# graphic_stereo.net
KiCad netlist of a schematic drawn in EAGLE
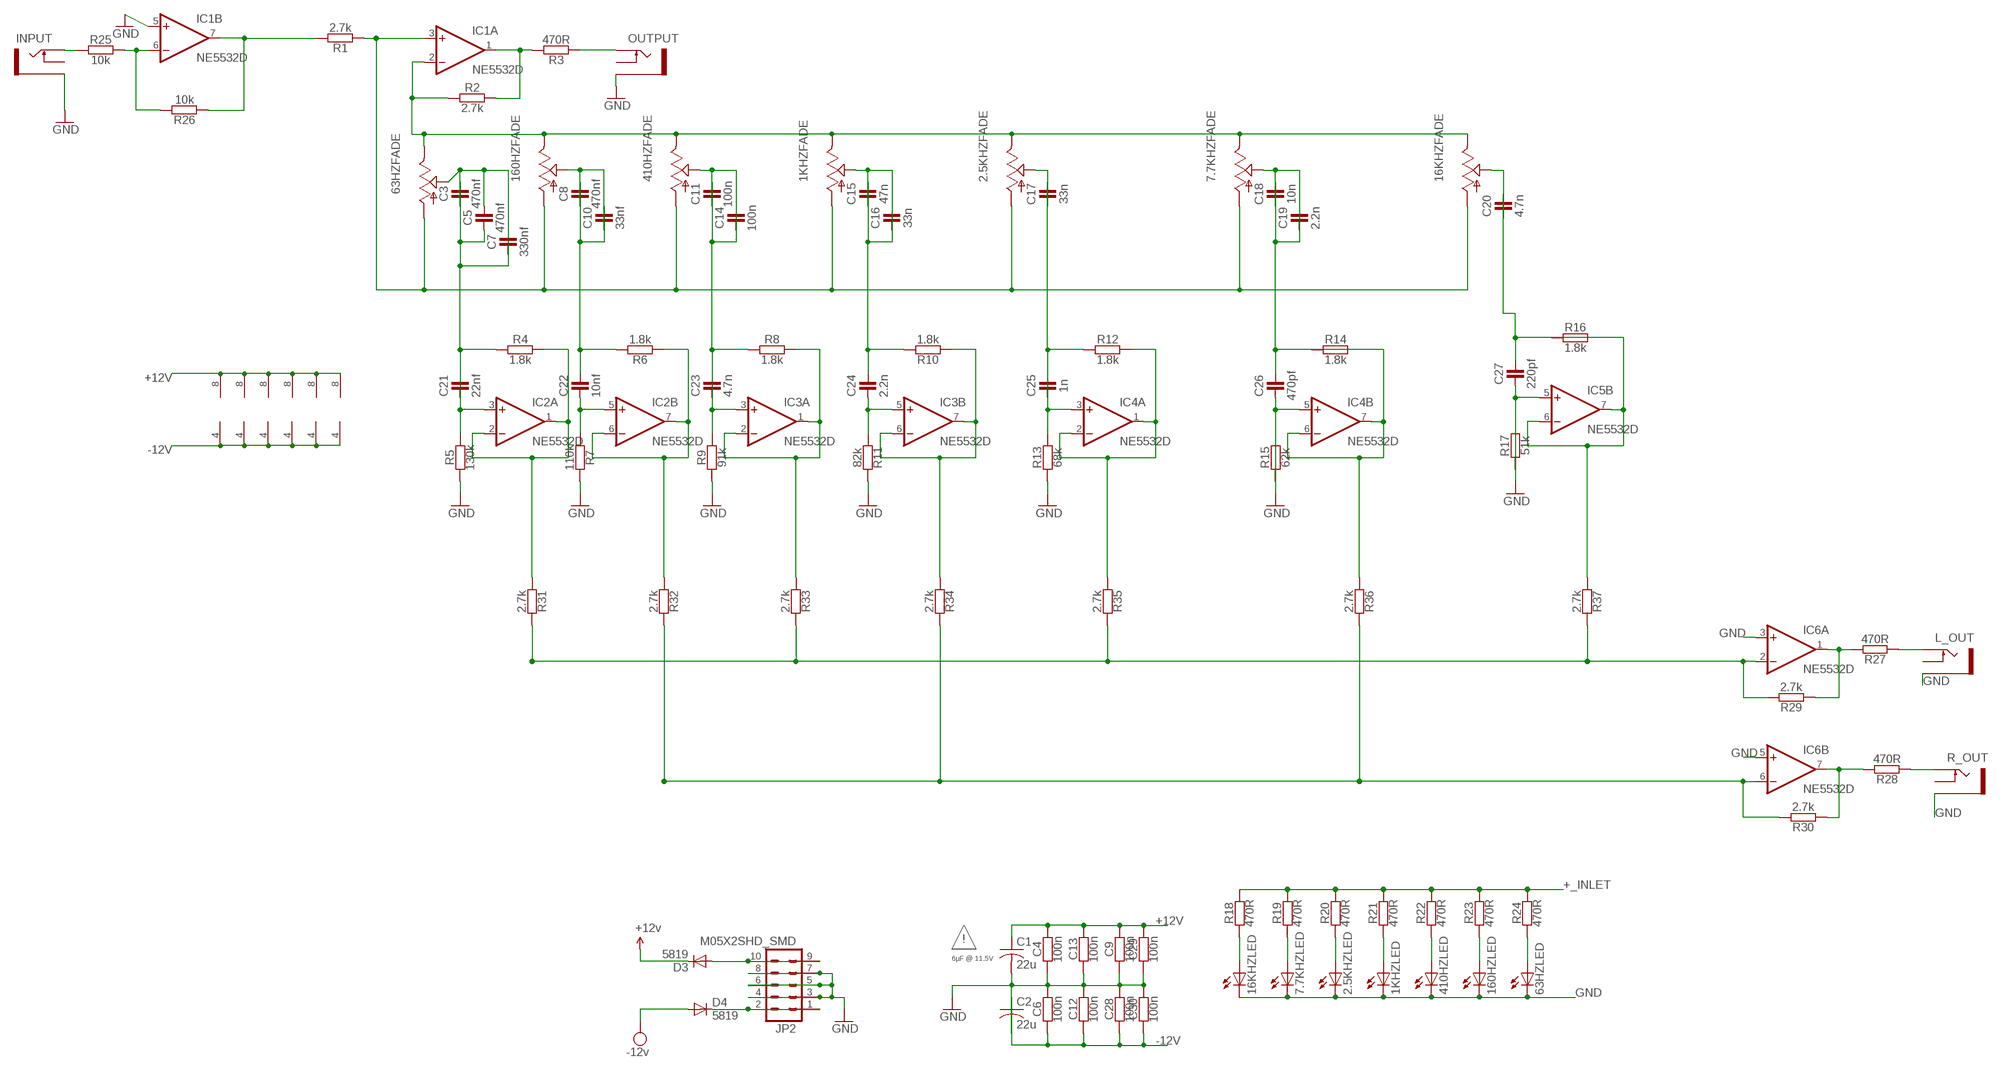
[diagram p0: schematic, sheet 1]

(export (version "E")
  (design (tool "Eeschema 10.0.6"))
  (components
    (comp (ref "1KHZ")
      (value "ALPHA_20MM_ILLUM_FADER")
      (footprint "eagle-import:ALPHA_ILL_FADER_20MM")
      (libsource (lib "eagle-import") (part "ALPHA_20MM_ILLUM_FADER"))
    )
    (comp (ref "2.5KHZ")
      (value "ALPHA_20MM_ILLUM_FADER")
      (footprint "eagle-import:ALPHA_ILL_FADER_20MM")
      (libsource (lib "eagle-import") (part "ALPHA_20MM_ILLUM_FADER"))
    )
    (comp (ref "7.7KHZ")
      (value "ALPHA_20MM_ILLUM_FADER")
      (footprint "eagle-import:ALPHA_ILL_FADER_20MM")
      (libsource (lib "eagle-import") (part "ALPHA_20MM_ILLUM_FADER"))
    )
    (comp (ref "16KHZ")
      (value "ALPHA_20MM_ILLUM_FADER")
      (footprint "eagle-import:ALPHA_ILL_FADER_20MM")
      (libsource (lib "eagle-import") (part "ALPHA_20MM_ILLUM_FADER"))
    )
    (comp (ref "63HZ")
      (value "ALPHA_20MM_ILLUM_FADER")
      (footprint "eagle-import:ALPHA_ILL_FADER_20MM")
      (libsource (lib "eagle-import") (part "ALPHA_20MM_ILLUM_FADER"))
    )
    (comp (ref "160HZ")
      (value "ALPHA_20MM_ILLUM_FADER")
      (footprint "eagle-import:ALPHA_ILL_FADER_20MM")
      (libsource (lib "eagle-import") (part "ALPHA_20MM_ILLUM_FADER"))
    )
    (comp (ref "410HZ")
      (value "ALPHA_20MM_ILLUM_FADER")
      (footprint "eagle-import:ALPHA_ILL_FADER_20MM")
      (libsource (lib "eagle-import") (part "ALPHA_20MM_ILLUM_FADER"))
    )
    (comp (ref "C1")
      (value "22u")
      (footprint "eagle-import:C1206")
      (libsource (lib "eagle-import") (part "C-USC1206"))
    )
    (comp (ref "C2")
      (value "22u")
      (footprint "eagle-import:C1206")
      (libsource (lib "eagle-import") (part "C-USC1206"))
    )
    (comp (ref "C3")
      (value "470nf")
      (footprint "eagle-import:C0805")
      (libsource (lib "eagle-import") (part "CAPACITOR-0805"))
    )
    (comp (ref "C4")
      (value "100n")
      (footprint "eagle-import:C0805")
      (libsource (lib "eagle-import") (part "RESISTOR-0805"))
    )
    (comp (ref "C5")
      (value "470nf")
      (footprint "eagle-import:C0805")
      (libsource (lib "eagle-import") (part "CAPACITOR-0805"))
    )
    (comp (ref "C6")
      (value "100n")
      (footprint "eagle-import:C0805")
      (libsource (lib "eagle-import") (part "RESISTOR-0805"))
    )
    (comp (ref "C7")
      (value "330nf")
      (footprint "eagle-import:C0805")
      (libsource (lib "eagle-import") (part "CAPACITOR-0805"))
    )
    (comp (ref "C8")
      (value "470nf")
      (footprint "eagle-import:C0805")
      (libsource (lib "eagle-import") (part "CAPACITOR-0805"))
    )
    (comp (ref "C9")
      (value "100n")
      (footprint "eagle-import:C0805")
      (libsource (lib "eagle-import") (part "RESISTOR-0805"))
    )
    (comp (ref "C10")
      (value "33nf")
      (footprint "eagle-import:C0805")
      (libsource (lib "eagle-import") (part "CAPACITOR-0805"))
    )
    (comp (ref "C11")
      (value "100n")
      (footprint "eagle-import:C0805")
      (libsource (lib "eagle-import") (part "CAPACITOR-0805"))
    )
    (comp (ref "C12")
      (value "100n")
      (footprint "eagle-import:C0805")
      (libsource (lib "eagle-import") (part "RESISTOR-0805"))
    )
    (comp (ref "C13")
      (value "100n")
      (footprint "eagle-import:C0805")
      (libsource (lib "eagle-import") (part "RESISTOR-0805"))
    )
    (comp (ref "C14")
      (value "100n")
      (footprint "eagle-import:C0805")
      (libsource (lib "eagle-import") (part "CAPACITOR-0805"))
    )
    (comp (ref "C15")
      (value "47n")
      (footprint "eagle-import:C0805")
      (libsource (lib "eagle-import") (part "CAPACITOR-0805"))
    )
    (comp (ref "C16")
      (value "33n")
      (footprint "eagle-import:C0805")
      (libsource (lib "eagle-import") (part "CAPACITOR-0805"))
    )
    (comp (ref "C17")
      (value "33n")
      (footprint "eagle-import:C0805")
      (libsource (lib "eagle-import") (part "CAPACITOR-0805"))
    )
    (comp (ref "C18")
      (value "10n")
      (footprint "eagle-import:C0805")
      (libsource (lib "eagle-import") (part "CAPACITOR-0805"))
    )
    (comp (ref "C19")
      (value "2.2n")
      (footprint "eagle-import:C0805")
      (libsource (lib "eagle-import") (part "CAPACITOR-0805"))
    )
    (comp (ref "C20")
      (value "4.7n")
      (footprint "eagle-import:C0805")
      (libsource (lib "eagle-import") (part "CAPACITOR-0805"))
    )
    (comp (ref "C21")
      (value "22nf")
      (footprint "eagle-import:C0805")
      (libsource (lib "eagle-import") (part "CAPACITOR-0805"))
    )
    (comp (ref "C22")
      (value "10nf")
      (footprint "eagle-import:C0805")
      (libsource (lib "eagle-import") (part "CAPACITOR-0805"))
    )
    (comp (ref "C23")
      (value "4.7n")
      (footprint "eagle-import:C0805")
      (libsource (lib "eagle-import") (part "CAPACITOR-0805"))
    )
    (comp (ref "C24")
      (value "2.2n")
      (footprint "eagle-import:C0805")
      (libsource (lib "eagle-import") (part "CAPACITOR-0805"))
    )
    (comp (ref "C25")
      (value "1n")
      (footprint "eagle-import:C0805")
      (libsource (lib "eagle-import") (part "CAPACITOR-0805"))
    )
    (comp (ref "C26")
      (value "470pf")
      (footprint "eagle-import:C0805")
      (libsource (lib "eagle-import") (part "CAPACITOR-0805"))
    )
    (comp (ref "C27")
      (value "220pf")
      (footprint "eagle-import:C0805")
      (libsource (lib "eagle-import") (part "CAPACITOR-0805"))
    )
    (comp (ref "C28")
      (value "100n")
      (footprint "eagle-import:C0805")
      (libsource (lib "eagle-import") (part "RESISTOR-0805"))
    )
    (comp (ref "C29")
      (value "100n")
      (footprint "eagle-import:C0805")
      (libsource (lib "eagle-import") (part "RESISTOR-0805"))
    )
    (comp (ref "C30")
      (value "100n")
      (footprint "eagle-import:C0805")
      (libsource (lib "eagle-import") (part "RESISTOR-0805"))
    )
    (comp (ref "D3")
      (value "5819")
      (footprint "eagle-import:SOD123")
      (libsource (lib "eagle-import") (part "DIODE-SOD123"))
    )
    (comp (ref "D4")
      (value "5819")
      (footprint "eagle-import:SOD123")
      (libsource (lib "eagle-import") (part "DIODE-SOD123"))
    )
    (comp (ref "IC1")
      (value "NE5532D")
      (footprint "eagle-import:SO08")
      (libsource (lib "eagle-import") (part "NE5532D"))
    )
    (comp (ref "IC2")
      (value "NE5532D")
      (footprint "eagle-import:SO08")
      (libsource (lib "eagle-import") (part "NE5532D"))
    )
    (comp (ref "IC3")
      (value "NE5532D")
      (footprint "eagle-import:SO08")
      (libsource (lib "eagle-import") (part "NE5532D"))
    )
    (comp (ref "IC4")
      (value "NE5532D")
      (footprint "eagle-import:SO08")
      (libsource (lib "eagle-import") (part "NE5532D"))
    )
    (comp (ref "IC5")
      (value "NE5532D")
      (footprint "eagle-import:SO08")
      (libsource (lib "eagle-import") (part "NE5532D"))
    )
    (comp (ref "IC6")
      (value "NE5532D")
      (footprint "eagle-import:SO08")
      (libsource (lib "eagle-import") (part "NE5532D"))
    )
    (comp (ref "INPUT")
      (value "THONKICONNNEW")
      (footprint "eagle-import:WQP-PJ301M-12_JACK")
      (libsource (lib "eagle-import") (part "THONKICONNNEW"))
    )
    (comp (ref "JP2")
      (value "M05X2SHD_SMD")
      (footprint "eagle-import:2X5-SHROUDED_SMD")
      (libsource (lib "eagle-import") (part "M05X2SHD_SMD"))
    )
    (comp (ref "L_OUT")
      (value "THONKICONNNEW")
      (footprint "eagle-import:WQP-PJ301M-12_JACK")
      (libsource (lib "eagle-import") (part "THONKICONNNEW"))
    )
    (comp (ref "OUTPUT")
      (value "THONKICONNNEW")
      (footprint "eagle-import:WQP-PJ301M-12_JACK")
      (libsource (lib "eagle-import") (part "THONKICONNNEW"))
    )
    (comp (ref "R1")
      (value "2.7k")
      (footprint "eagle-import:C0805")
      (libsource (lib "eagle-import") (part "RESISTOR-0805"))
    )
    (comp (ref "R2")
      (value "2.7k")
      (footprint "eagle-import:C0805")
      (libsource (lib "eagle-import") (part "RESISTOR-0805"))
    )
    (comp (ref "R3")
      (value "470R")
      (footprint "eagle-import:C0805")
      (libsource (lib "eagle-import") (part "RESISTOR-0805"))
    )
    (comp (ref "R4")
      (value "1.8k")
      (footprint "eagle-import:C0805")
      (libsource (lib "eagle-import") (part "RESISTOR-0805"))
    )
    (comp (ref "R5")
      (value "130k")
      (footprint "eagle-import:C0805")
      (libsource (lib "eagle-import") (part "RESISTOR-0805"))
    )
    (comp (ref "R6")
      (value "1.8k")
      (footprint "eagle-import:C0805")
      (libsource (lib "eagle-import") (part "RESISTOR-0805"))
    )
    (comp (ref "R7")
      (value "110k")
      (footprint "eagle-import:C0805")
      (libsource (lib "eagle-import") (part "RESISTOR-0805"))
    )
    (comp (ref "R8")
      (value "1.8k")
      (footprint "eagle-import:C0805")
      (libsource (lib "eagle-import") (part "RESISTOR-0805"))
    )
    (comp (ref "R9")
      (value "91k")
      (footprint "eagle-import:C0805")
      (libsource (lib "eagle-import") (part "RESISTOR-0805"))
    )
    (comp (ref "R10")
      (value "1.8k")
      (footprint "eagle-import:C0805")
      (libsource (lib "eagle-import") (part "RESISTOR-0805"))
    )
    (comp (ref "R11")
      (value "82k")
      (footprint "eagle-import:C0805")
      (libsource (lib "eagle-import") (part "RESISTOR-0805"))
    )
    (comp (ref "R12")
      (value "1.8k")
      (footprint "eagle-import:C0805")
      (libsource (lib "eagle-import") (part "RESISTOR-0805"))
    )
    (comp (ref "R13")
      (value "68k")
      (footprint "eagle-import:C0805")
      (libsource (lib "eagle-import") (part "RESISTOR-0805"))
    )
    (comp (ref "R14")
      (value "1.8k")
      (footprint "eagle-import:C0805")
      (libsource (lib "eagle-import") (part "RESISTOR-0805"))
    )
    (comp (ref "R15")
      (value "62k")
      (footprint "eagle-import:C0805")
      (libsource (lib "eagle-import") (part "RESISTOR-0805"))
    )
    (comp (ref "R16")
      (value "1.8k")
      (footprint "eagle-import:C0805")
      (libsource (lib "eagle-import") (part "RESISTOR-0805"))
    )
    (comp (ref "R17")
      (value "51k")
      (footprint "eagle-import:C0805")
      (libsource (lib "eagle-import") (part "RESISTOR-0805"))
    )
    (comp (ref "R18")
      (value "470R")
      (footprint "eagle-import:C0805")
      (libsource (lib "eagle-import") (part "RESISTOR-0805"))
    )
    (comp (ref "R19")
      (value "470R")
      (footprint "eagle-import:C0805")
      (libsource (lib "eagle-import") (part "RESISTOR-0805"))
    )
    (comp (ref "R20")
      (value "470R")
      (footprint "eagle-import:C0805")
      (libsource (lib "eagle-import") (part "RESISTOR-0805"))
    )
    (comp (ref "R21")
      (value "470R")
      (footprint "eagle-import:C0805")
      (libsource (lib "eagle-import") (part "RESISTOR-0805"))
    )
    (comp (ref "R22")
      (value "470R")
      (footprint "eagle-import:C0805")
      (libsource (lib "eagle-import") (part "RESISTOR-0805"))
    )
    (comp (ref "R23")
      (value "470R")
      (footprint "eagle-import:C0805")
      (libsource (lib "eagle-import") (part "RESISTOR-0805"))
    )
    (comp (ref "R24")
      (value "470R")
      (footprint "eagle-import:C0805")
      (libsource (lib "eagle-import") (part "RESISTOR-0805"))
    )
    (comp (ref "R25")
      (value "10k")
      (footprint "eagle-import:C0805")
      (libsource (lib "eagle-import") (part "RESISTOR-0805"))
    )
    (comp (ref "R26")
      (value "10k")
      (footprint "eagle-import:C0805")
      (libsource (lib "eagle-import") (part "RESISTOR-0805"))
    )
    (comp (ref "R27")
      (value "470R")
      (footprint "eagle-import:C0805")
      (libsource (lib "eagle-import") (part "RESISTOR-0805"))
    )
    (comp (ref "R28")
      (value "470R")
      (footprint "eagle-import:C0805")
      (libsource (lib "eagle-import") (part "RESISTOR-0805"))
    )
    (comp (ref "R29")
      (value "2.7k")
      (footprint "eagle-import:C0805")
      (libsource (lib "eagle-import") (part "RESISTOR-0805"))
    )
    (comp (ref "R30")
      (value "2.7k")
      (footprint "eagle-import:C0805")
      (libsource (lib "eagle-import") (part "RESISTOR-0805"))
    )
    (comp (ref "R31")
      (value "2.7k")
      (footprint "eagle-import:C0805")
      (libsource (lib "eagle-import") (part "RESISTOR-0805"))
    )
    (comp (ref "R32")
      (value "2.7k")
      (footprint "eagle-import:C0805")
      (libsource (lib "eagle-import") (part "RESISTOR-0805"))
    )
    (comp (ref "R33")
      (value "2.7k")
      (footprint "eagle-import:C0805")
      (libsource (lib "eagle-import") (part "RESISTOR-0805"))
    )
    (comp (ref "R34")
      (value "2.7k")
      (footprint "eagle-import:C0805")
      (libsource (lib "eagle-import") (part "RESISTOR-0805"))
    )
    (comp (ref "R35")
      (value "2.7k")
      (footprint "eagle-import:C0805")
      (libsource (lib "eagle-import") (part "RESISTOR-0805"))
    )
    (comp (ref "R36")
      (value "2.7k")
      (footprint "eagle-import:C0805")
      (libsource (lib "eagle-import") (part "RESISTOR-0805"))
    )
    (comp (ref "R37")
      (value "2.7k")
      (footprint "eagle-import:C0805")
      (libsource (lib "eagle-import") (part "RESISTOR-0805"))
    )
    (comp (ref "R_OUT")
      (value "THONKICONNNEW")
      (footprint "eagle-import:WQP-PJ301M-12_JACK")
      (libsource (lib "eagle-import") (part "THONKICONNNEW"))
    )
  )
  (nets
    (net (code "1") (name "+12v") (class "Default")
      (node (ref "C1") (pin "1") (pinfunction "1_1") (pintype "passive"))
      (node (ref "C13") (pin "2") (pinfunction "2_2") (pintype "passive"))
      (node (ref "C29") (pin "2") (pinfunction "2_2") (pintype "passive"))
      (node (ref "C4") (pin "2") (pinfunction "2_2") (pintype "passive"))
      (node (ref "C9") (pin "2") (pinfunction "2_2") (pintype "passive"))
      (node (ref "D3") (pin "C") (pinfunction "C_C") (pintype "passive"))
      (node (ref "IC1") (pin "8") (pinfunction "V+_8") (pintype "power_in"))
      (node (ref "IC2") (pin "8") (pinfunction "V+_8") (pintype "power_in"))
      (node (ref "IC3") (pin "8") (pinfunction "V+_8") (pintype "power_in"))
      (node (ref "IC4") (pin "8") (pinfunction "V+_8") (pintype "power_in"))
      (node (ref "IC5") (pin "8") (pinfunction "V+_8") (pintype "power_in"))
      (node (ref "IC6") (pin "8") (pinfunction "V+_8") (pintype "power_in"))
    )
    (net (code "2") (name "-12v") (class "Default")
      (node (ref "C12") (pin "1") (pinfunction "1_1") (pintype "passive"))
      (node (ref "C2") (pin "1") (pinfunction "1_1") (pintype "passive"))
      (node (ref "C28") (pin "1") (pinfunction "1_1") (pintype "passive"))
      (node (ref "C30") (pin "1") (pinfunction "1_1") (pintype "passive"))
      (node (ref "C6") (pin "1") (pinfunction "1_1") (pintype "passive"))
      (node (ref "D4") (pin "A") (pinfunction "A_A") (pintype "passive"))
      (node (ref "IC1") (pin "4") (pinfunction "V-_4") (pintype "power_in"))
      (node (ref "IC2") (pin "4") (pinfunction "V-_4") (pintype "power_in"))
      (node (ref "IC3") (pin "4") (pinfunction "V-_4") (pintype "power_in"))
      (node (ref "IC4") (pin "4") (pinfunction "V-_4") (pintype "power_in"))
      (node (ref "IC5") (pin "4") (pinfunction "V-_4") (pintype "power_in"))
      (node (ref "IC6") (pin "4") (pinfunction "V-_4") (pintype "power_in"))
    )
    (net (code "3") (name "/+_INLET") (class "Default")
      (node (ref "D3") (pin "A") (pinfunction "A_A") (pintype "passive"))
      (node (ref "JP2") (pin "10") (pinfunction "10_10") (pintype "passive"))
      (node (ref "JP2") (pin "9") (pinfunction "9_9") (pintype "passive"))
      (node (ref "R18") (pin "2") (pinfunction "2_2") (pintype "passive"))
      (node (ref "R19") (pin "2") (pinfunction "2_2") (pintype "passive"))
      (node (ref "R20") (pin "2") (pinfunction "2_2") (pintype "passive"))
      (node (ref "R21") (pin "2") (pinfunction "2_2") (pintype "passive"))
      (node (ref "R22") (pin "2") (pinfunction "2_2") (pintype "passive"))
      (node (ref "R23") (pin "2") (pinfunction "2_2") (pintype "passive"))
      (node (ref "R24") (pin "2") (pinfunction "2_2") (pintype "passive"))
    )
    (net (code "4") (name "GND") (class "Default")
      (node (ref "160HZ") (pin "E") (pinfunction "C_E") (pintype "passive"))
      (node (ref "16KHZ") (pin "E") (pinfunction "C_E") (pintype "passive"))
      (node (ref "1KHZ") (pin "E") (pinfunction "C_E") (pintype "passive"))
      (node (ref "2.5KHZ") (pin "E") (pinfunction "C_E") (pintype "passive"))
      (node (ref "410HZ") (pin "E") (pinfunction "C_E") (pintype "passive"))
      (node (ref "63HZ") (pin "E") (pinfunction "C_E") (pintype "passive"))
      (node (ref "7.7KHZ") (pin "E") (pinfunction "C_E") (pintype "passive"))
      (node (ref "C1") (pin "2") (pinfunction "2_2") (pintype "passive"))
      (node (ref "C12") (pin "2") (pinfunction "2_2") (pintype "passive"))
      (node (ref "C13") (pin "1") (pinfunction "1_1") (pintype "passive"))
      (node (ref "C2") (pin "2") (pinfunction "2_2") (pintype "passive"))
      (node (ref "C28") (pin "2") (pinfunction "2_2") (pintype "passive"))
      (node (ref "C29") (pin "1") (pinfunction "1_1") (pintype "passive"))
      (node (ref "C30") (pin "2") (pinfunction "2_2") (pintype "passive"))
      (node (ref "C4") (pin "1") (pinfunction "1_1") (pintype "passive"))
      (node (ref "C6") (pin "2") (pinfunction "2_2") (pintype "passive"))
      (node (ref "C9") (pin "1") (pinfunction "1_1") (pintype "passive"))
      (node (ref "IC1") (pin "5") (pinfunction "+IN_5") (pintype "input"))
      (node (ref "IC6") (pin "3") (pinfunction "+IN_3") (pintype "input"))
      (node (ref "IC6") (pin "5") (pinfunction "+IN_5") (pintype "input"))
      (node (ref "INPUT") (pin "P$3_SLEEVE") (pinfunction "SLEEVE_P$3_SLEEVE") (pintype "passive"))
      (node (ref "JP2") (pin "3") (pinfunction "3_3") (pintype "passive"))
      (node (ref "JP2") (pin "4") (pinfunction "4_4") (pintype "passive"))
      (node (ref "JP2") (pin "5") (pinfunction "5_5") (pintype "passive"))
      (node (ref "JP2") (pin "6") (pinfunction "6_6") (pintype "passive"))
      (node (ref "JP2") (pin "7") (pinfunction "7_7") (pintype "passive"))
      (node (ref "JP2") (pin "8") (pinfunction "8_8") (pintype "passive"))
      (node (ref "L_OUT") (pin "P$3_SLEEVE") (pinfunction "SLEEVE_P$3_SLEEVE") (pintype "passive"))
      (node (ref "OUTPUT") (pin "P$3_SLEEVE") (pinfunction "SLEEVE_P$3_SLEEVE") (pintype "passive"))
      (node (ref "R11") (pin "2") (pinfunction "2_2") (pintype "passive"))
      (node (ref "R13") (pin "1") (pinfunction "1_1") (pintype "passive"))
      (node (ref "R15") (pin "2") (pinfunction "2_2") (pintype "passive"))
      (node (ref "R17") (pin "2") (pinfunction "2_2") (pintype "passive"))
      (node (ref "R5") (pin "1") (pinfunction "1_1") (pintype "passive"))
      (node (ref "R7") (pin "2") (pinfunction "2_2") (pintype "passive"))
      (node (ref "R9") (pin "1") (pinfunction "1_1") (pintype "passive"))
      (node (ref "R_OUT") (pin "P$3_SLEEVE") (pinfunction "SLEEVE_P$3_SLEEVE") (pintype "passive"))
    )
    (net (code "5") (name "Net-(1KHZA-S)") (class "Default")
      (node (ref "1KHZ") (pin "2") (pinfunction "S_2") (pintype "passive"))
      (node (ref "C15") (pin "1") (pinfunction "1_1") (pintype "passive"))
      (node (ref "C16") (pin "1") (pinfunction "1_1") (pintype "passive"))
    )
    (net (code "6") (name "Net-(1KHZB-A)") (class "Default")
      (node (ref "1KHZ") (pin "B") (pinfunction "A_B") (pintype "passive"))
      (node (ref "R21") (pin "1") (pinfunction "1_1") (pintype "passive"))
    )
    (net (code "7") (name "Net-(2.5KHZA-S)") (class "Default")
      (node (ref "2.5KHZ") (pin "2") (pinfunction "S_2") (pintype "passive"))
      (node (ref "C17") (pin "1") (pinfunction "1_1") (pintype "passive"))
    )
    (net (code "8") (name "Net-(2.5KHZB-A)") (class "Default")
      (node (ref "2.5KHZ") (pin "B") (pinfunction "A_B") (pintype "passive"))
      (node (ref "R20") (pin "1") (pinfunction "1_1") (pintype "passive"))
    )
    (net (code "9") (name "Net-(7.7KHZA-S)") (class "Default")
      (node (ref "7.7KHZ") (pin "2") (pinfunction "S_2") (pintype "passive"))
      (node (ref "C18") (pin "1") (pinfunction "1_1") (pintype "passive"))
      (node (ref "C19") (pin "1") (pinfunction "1_1") (pintype "passive"))
    )
    (net (code "10") (name "Net-(7.7KHZB-A)") (class "Default")
      (node (ref "7.7KHZ") (pin "B") (pinfunction "A_B") (pintype "passive"))
      (node (ref "R19") (pin "1") (pinfunction "1_1") (pintype "passive"))
    )
    (net (code "11") (name "Net-(16KHZA-S)") (class "Default")
      (node (ref "16KHZ") (pin "2") (pinfunction "S_2") (pintype "passive"))
      (node (ref "C20") (pin "1") (pinfunction "1_1") (pintype "passive"))
    )
    (net (code "12") (name "Net-(16KHZB-A)") (class "Default")
      (node (ref "16KHZ") (pin "B") (pinfunction "A_B") (pintype "passive"))
      (node (ref "R18") (pin "1") (pinfunction "1_1") (pintype "passive"))
    )
    (net (code "13") (name "Net-(63HZA-S)") (class "Default")
      (node (ref "63HZ") (pin "2") (pinfunction "S_2") (pintype "passive"))
      (node (ref "C3") (pin "1") (pinfunction "1_1") (pintype "passive"))
      (node (ref "C5") (pin "2") (pinfunction "2_2") (pintype "passive"))
      (node (ref "C7") (pin "1") (pinfunction "1_1") (pintype "passive"))
    )
    (net (code "14") (name "Net-(63HZB-A)") (class "Default")
      (node (ref "63HZ") (pin "B") (pinfunction "A_B") (pintype "passive"))
      (node (ref "R24") (pin "1") (pinfunction "1_1") (pintype "passive"))
    )
    (net (code "15") (name "Net-(160HZA-A)") (class "Default")
      (node (ref "160HZ") (pin "3") (pinfunction "A_3") (pintype "passive"))
      (node (ref "16KHZ") (pin "3") (pinfunction "A_3") (pintype "passive"))
      (node (ref "1KHZ") (pin "3") (pinfunction "A_3") (pintype "passive"))
      (node (ref "2.5KHZ") (pin "3") (pinfunction "A_3") (pintype "passive"))
      (node (ref "410HZ") (pin "3") (pinfunction "A_3") (pintype "passive"))
      (node (ref "63HZ") (pin "3") (pinfunction "A_3") (pintype "passive"))
      (node (ref "7.7KHZ") (pin "3") (pinfunction "A_3") (pintype "passive"))
      (node (ref "IC1") (pin "3") (pinfunction "+IN_3") (pintype "input"))
      (node (ref "R1") (pin "1") (pinfunction "1_1") (pintype "passive"))
    )
    (net (code "16") (name "Net-(160HZA-E)") (class "Default")
      (node (ref "160HZ") (pin "1") (pinfunction "E_1") (pintype "passive"))
      (node (ref "16KHZ") (pin "1") (pinfunction "E_1") (pintype "passive"))
      (node (ref "1KHZ") (pin "1") (pinfunction "E_1") (pintype "passive"))
      (node (ref "2.5KHZ") (pin "1") (pinfunction "E_1") (pintype "passive"))
      (node (ref "410HZ") (pin "1") (pinfunction "E_1") (pintype "passive"))
      (node (ref "63HZ") (pin "1") (pinfunction "E_1") (pintype "passive"))
      (node (ref "7.7KHZ") (pin "1") (pinfunction "E_1") (pintype "passive"))
      (node (ref "IC1") (pin "2") (pinfunction "-IN_2") (pintype "input"))
      (node (ref "R2") (pin "1") (pinfunction "1_1") (pintype "passive"))
    )
    (net (code "17") (name "Net-(160HZA-S)") (class "Default")
      (node (ref "160HZ") (pin "2") (pinfunction "S_2") (pintype "passive"))
      (node (ref "C10") (pin "1") (pinfunction "1_1") (pintype "passive"))
      (node (ref "C8") (pin "1") (pinfunction "1_1") (pintype "passive"))
    )
    (net (code "18") (name "Net-(160HZB-A)") (class "Default")
      (node (ref "160HZ") (pin "B") (pinfunction "A_B") (pintype "passive"))
      (node (ref "R23") (pin "1") (pinfunction "1_1") (pintype "passive"))
    )
    (net (code "19") (name "Net-(410HZA-S)") (class "Default")
      (node (ref "410HZ") (pin "2") (pinfunction "S_2") (pintype "passive"))
      (node (ref "C11") (pin "1") (pinfunction "1_1") (pintype "passive"))
      (node (ref "C14") (pin "1") (pinfunction "1_1") (pintype "passive"))
    )
    (net (code "20") (name "Net-(410HZB-A)") (class "Default")
      (node (ref "410HZ") (pin "B") (pinfunction "A_B") (pintype "passive"))
      (node (ref "R22") (pin "1") (pinfunction "1_1") (pintype "passive"))
    )
    (net (code "21") (name "Net-(C10-Pad2)") (class "Default")
      (node (ref "C10") (pin "2") (pinfunction "2_2") (pintype "passive"))
      (node (ref "C22") (pin "2") (pinfunction "2_2") (pintype "passive"))
      (node (ref "C8") (pin "2") (pinfunction "2_2") (pintype "passive"))
      (node (ref "R6") (pin "2") (pinfunction "2_2") (pintype "passive"))
    )
    (net (code "22") (name "Net-(C11-Pad2)") (class "Default")
      (node (ref "C11") (pin "2") (pinfunction "2_2") (pintype "passive"))
      (node (ref "C14") (pin "2") (pinfunction "2_2") (pintype "passive"))
      (node (ref "C23") (pin "1") (pinfunction "1_1") (pintype "passive"))
      (node (ref "R8") (pin "1") (pinfunction "1_1") (pintype "passive"))
    )
    (net (code "23") (name "Net-(C15-Pad2)") (class "Default")
      (node (ref "C15") (pin "2") (pinfunction "2_2") (pintype "passive"))
      (node (ref "C16") (pin "2") (pinfunction "2_2") (pintype "passive"))
      (node (ref "C24") (pin "2") (pinfunction "2_2") (pintype "passive"))
      (node (ref "R10") (pin "2") (pinfunction "2_2") (pintype "passive"))
    )
    (net (code "24") (name "Net-(C17-Pad2)") (class "Default")
      (node (ref "C17") (pin "2") (pinfunction "2_2") (pintype "passive"))
      (node (ref "C25") (pin "1") (pinfunction "1_1") (pintype "passive"))
      (node (ref "R12") (pin "1") (pinfunction "1_1") (pintype "passive"))
    )
    (net (code "25") (name "Net-(C18-Pad2)") (class "Default")
      (node (ref "C18") (pin "2") (pinfunction "2_2") (pintype "passive"))
      (node (ref "C19") (pin "2") (pinfunction "2_2") (pintype "passive"))
      (node (ref "C26") (pin "2") (pinfunction "2_2") (pintype "passive"))
      (node (ref "R14") (pin "2") (pinfunction "2_2") (pintype "passive"))
    )
    (net (code "26") (name "Net-(C20-Pad2)") (class "Default")
      (node (ref "C20") (pin "2") (pinfunction "2_2") (pintype "passive"))
      (node (ref "C27") (pin "2") (pinfunction "2_2") (pintype "passive"))
      (node (ref "R16") (pin "2") (pinfunction "2_2") (pintype "passive"))
    )
    (net (code "27") (name "Net-(C21-Pad1)") (class "Default")
      (node (ref "C21") (pin "1") (pinfunction "1_1") (pintype "passive"))
      (node (ref "C3") (pin "2") (pinfunction "2_2") (pintype "passive"))
      (node (ref "C5") (pin "1") (pinfunction "1_1") (pintype "passive"))
      (node (ref "C7") (pin "2") (pinfunction "2_2") (pintype "passive"))
      (node (ref "R4") (pin "1") (pinfunction "1_1") (pintype "passive"))
    )
    (net (code "28") (name "Net-(D4-PadC)") (class "Default")
      (node (ref "D4") (pin "C") (pinfunction "C_C") (pintype "passive"))
      (node (ref "JP2") (pin "1") (pinfunction "1_1") (pintype "passive"))
      (node (ref "JP2") (pin "2") (pinfunction "2_2") (pintype "passive"))
    )
    (net (code "29") (name "Net-(IC1A-OUT)") (class "Default")
      (node (ref "IC1") (pin "1") (pinfunction "OUT_1") (pintype "output"))
      (node (ref "R2") (pin "2") (pinfunction "2_2") (pintype "passive"))
      (node (ref "R3") (pin "2") (pinfunction "2_2") (pintype "passive"))
    )
    (net (code "30") (name "Net-(IC1B--IN)") (class "Default")
      (node (ref "IC1") (pin "6") (pinfunction "-IN_6") (pintype "input"))
      (node (ref "R25") (pin "2") (pinfunction "2_2") (pintype "passive"))
      (node (ref "R26") (pin "2") (pinfunction "2_2") (pintype "passive"))
    )
    (net (code "31") (name "Net-(IC1B-OUT)") (class "Default")
      (node (ref "IC1") (pin "7") (pinfunction "OUT_7") (pintype "output"))
      (node (ref "R1") (pin "2") (pinfunction "2_2") (pintype "passive"))
      (node (ref "R26") (pin "1") (pinfunction "1_1") (pintype "passive"))
    )
    (net (code "32") (name "Net-(IC2A-+IN)") (class "Default")
      (node (ref "C21") (pin "2") (pinfunction "2_2") (pintype "passive"))
      (node (ref "IC2") (pin "3") (pinfunction "+IN_3") (pintype "input"))
      (node (ref "R5") (pin "2") (pinfunction "2_2") (pintype "passive"))
    )
    (net (code "33") (name "Net-(IC2A--IN)") (class "Default")
      (node (ref "IC2") (pin "1") (pinfunction "OUT_1") (pintype "output"))
      (node (ref "IC2") (pin "2") (pinfunction "-IN_2") (pintype "input"))
      (node (ref "R31") (pin "1") (pinfunction "1_1") (pintype "passive"))
      (node (ref "R4") (pin "2") (pinfunction "2_2") (pintype "passive"))
    )
    (net (code "34") (name "Net-(IC2B-+IN)") (class "Default")
      (node (ref "C22") (pin "1") (pinfunction "1_1") (pintype "passive"))
      (node (ref "IC2") (pin "5") (pinfunction "+IN_5") (pintype "input"))
      (node (ref "R7") (pin "1") (pinfunction "1_1") (pintype "passive"))
    )
    (net (code "35") (name "Net-(IC2B--IN)") (class "Default")
      (node (ref "IC2") (pin "6") (pinfunction "-IN_6") (pintype "input"))
      (node (ref "IC2") (pin "7") (pinfunction "OUT_7") (pintype "output"))
      (node (ref "R32") (pin "1") (pinfunction "1_1") (pintype "passive"))
      (node (ref "R6") (pin "1") (pinfunction "1_1") (pintype "passive"))
    )
    (net (code "36") (name "Net-(IC3A-+IN)") (class "Default")
      (node (ref "C23") (pin "2") (pinfunction "2_2") (pintype "passive"))
      (node (ref "IC3") (pin "3") (pinfunction "+IN_3") (pintype "input"))
      (node (ref "R9") (pin "2") (pinfunction "2_2") (pintype "passive"))
    )
    (net (code "37") (name "Net-(IC3A--IN)") (class "Default")
      (node (ref "IC3") (pin "1") (pinfunction "OUT_1") (pintype "output"))
      (node (ref "IC3") (pin "2") (pinfunction "-IN_2") (pintype "input"))
      (node (ref "R33") (pin "1") (pinfunction "1_1") (pintype "passive"))
      (node (ref "R8") (pin "2") (pinfunction "2_2") (pintype "passive"))
    )
    (net (code "38") (name "Net-(IC3B-+IN)") (class "Default")
      (node (ref "C24") (pin "1") (pinfunction "1_1") (pintype "passive"))
      (node (ref "IC3") (pin "5") (pinfunction "+IN_5") (pintype "input"))
      (node (ref "R11") (pin "1") (pinfunction "1_1") (pintype "passive"))
    )
    (net (code "39") (name "Net-(IC3B--IN)") (class "Default")
      (node (ref "IC3") (pin "6") (pinfunction "-IN_6") (pintype "input"))
      (node (ref "IC3") (pin "7") (pinfunction "OUT_7") (pintype "output"))
      (node (ref "R10") (pin "1") (pinfunction "1_1") (pintype "passive"))
      (node (ref "R34") (pin "1") (pinfunction "1_1") (pintype "passive"))
    )
    (net (code "40") (name "Net-(IC4A-+IN)") (class "Default")
      (node (ref "C25") (pin "2") (pinfunction "2_2") (pintype "passive"))
      (node (ref "IC4") (pin "3") (pinfunction "+IN_3") (pintype "input"))
      (node (ref "R13") (pin "2") (pinfunction "2_2") (pintype "passive"))
    )
    (net (code "41") (name "Net-(IC4A--IN)") (class "Default")
      (node (ref "IC4") (pin "1") (pinfunction "OUT_1") (pintype "output"))
      (node (ref "IC4") (pin "2") (pinfunction "-IN_2") (pintype "input"))
      (node (ref "R12") (pin "2") (pinfunction "2_2") (pintype "passive"))
      (node (ref "R35") (pin "1") (pinfunction "1_1") (pintype "passive"))
    )
    (net (code "42") (name "Net-(IC4B-+IN)") (class "Default")
      (node (ref "C26") (pin "1") (pinfunction "1_1") (pintype "passive"))
      (node (ref "IC4") (pin "5") (pinfunction "+IN_5") (pintype "input"))
      (node (ref "R15") (pin "1") (pinfunction "1_1") (pintype "passive"))
    )
    (net (code "43") (name "Net-(IC4B--IN)") (class "Default")
      (node (ref "IC4") (pin "6") (pinfunction "-IN_6") (pintype "input"))
      (node (ref "IC4") (pin "7") (pinfunction "OUT_7") (pintype "output"))
      (node (ref "R14") (pin "1") (pinfunction "1_1") (pintype "passive"))
      (node (ref "R36") (pin "1") (pinfunction "1_1") (pintype "passive"))
    )
    (net (code "44") (name "Net-(IC5B-+IN)") (class "Default")
      (node (ref "C27") (pin "1") (pinfunction "1_1") (pintype "passive"))
      (node (ref "IC5") (pin "5") (pinfunction "+IN_5") (pintype "input"))
      (node (ref "R17") (pin "1") (pinfunction "1_1") (pintype "passive"))
    )
    (net (code "45") (name "Net-(IC5B--IN)") (class "Default")
      (node (ref "IC5") (pin "6") (pinfunction "-IN_6") (pintype "input"))
      (node (ref "IC5") (pin "7") (pinfunction "OUT_7") (pintype "output"))
      (node (ref "R16") (pin "1") (pinfunction "1_1") (pintype "passive"))
      (node (ref "R37") (pin "1") (pinfunction "1_1") (pintype "passive"))
    )
    (net (code "46") (name "Net-(IC6A--IN)") (class "Default")
      (node (ref "IC6") (pin "2") (pinfunction "-IN_2") (pintype "input"))
      (node (ref "R29") (pin "2") (pinfunction "2_2") (pintype "passive"))
      (node (ref "R31") (pin "2") (pinfunction "2_2") (pintype "passive"))
      (node (ref "R33") (pin "2") (pinfunction "2_2") (pintype "passive"))
      (node (ref "R35") (pin "2") (pinfunction "2_2") (pintype "passive"))
      (node (ref "R37") (pin "2") (pinfunction "2_2") (pintype "passive"))
    )
    (net (code "47") (name "Net-(IC6A-OUT)") (class "Default")
      (node (ref "IC6") (pin "1") (pinfunction "OUT_1") (pintype "output"))
      (node (ref "R27") (pin "2") (pinfunction "2_2") (pintype "passive"))
      (node (ref "R29") (pin "1") (pinfunction "1_1") (pintype "passive"))
    )
    (net (code "48") (name "Net-(IC6B--IN)") (class "Default")
      (node (ref "IC6") (pin "6") (pinfunction "-IN_6") (pintype "input"))
      (node (ref "R30") (pin "2") (pinfunction "2_2") (pintype "passive"))
      (node (ref "R32") (pin "2") (pinfunction "2_2") (pintype "passive"))
      (node (ref "R34") (pin "2") (pinfunction "2_2") (pintype "passive"))
      (node (ref "R36") (pin "2") (pinfunction "2_2") (pintype "passive"))
    )
    (net (code "49") (name "Net-(IC6B-OUT)") (class "Default")
      (node (ref "IC6") (pin "7") (pinfunction "OUT_7") (pintype "output"))
      (node (ref "R28") (pin "2") (pinfunction "2_2") (pintype "passive"))
      (node (ref "R30") (pin "1") (pinfunction "1_1") (pintype "passive"))
    )
    (net (code "50") (name "Net-(INPUT-TIP)") (class "Default")
      (node (ref "INPUT") (pin "P$1_TIP") (pinfunction "TIP_P$1_TIP") (pintype "passive"))
      (node (ref "R25") (pin "1") (pinfunction "1_1") (pintype "passive"))
    )
    (net (code "51") (name "Net-(L_OUT-TIP)") (class "Default")
      (node (ref "L_OUT") (pin "P$1_TIP") (pinfunction "TIP_P$1_TIP") (pintype "passive"))
      (node (ref "R27") (pin "1") (pinfunction "1_1") (pintype "passive"))
    )
    (net (code "52") (name "Net-(OUTPUT-TIP)") (class "Default")
      (node (ref "OUTPUT") (pin "P$1_TIP") (pinfunction "TIP_P$1_TIP") (pintype "passive"))
      (node (ref "R3") (pin "1") (pinfunction "1_1") (pintype "passive"))
    )
    (net (code "53") (name "Net-(R_OUT-TIP)") (class "Default")
      (node (ref "R28") (pin "1") (pinfunction "1_1") (pintype "passive"))
      (node (ref "R_OUT") (pin "P$1_TIP") (pinfunction "TIP_P$1_TIP") (pintype "passive"))
    )
    (net (code "54") (name "unconnected-(INPUT-SWITCH-PadP$2_SWITCH)") (class "Default")
      (node (ref "INPUT") (pin "P$2_SWITCH") (pinfunction "SWITCH_P$2_SWITCH") (pintype "passive"))
    )
    (net (code "55") (name "unconnected-(L_OUT-SWITCH-PadP$2_SWITCH)") (class "Default")
      (node (ref "L_OUT") (pin "P$2_SWITCH") (pinfunction "SWITCH_P$2_SWITCH") (pintype "passive"))
    )
    (net (code "56") (name "unconnected-(OUTPUT-SWITCH-PadP$2_SWITCH)") (class "Default")
      (node (ref "OUTPUT") (pin "P$2_SWITCH") (pinfunction "SWITCH_P$2_SWITCH") (pintype "passive"))
    )
    (net (code "57") (name "unconnected-(R_OUT-SWITCH-PadP$2_SWITCH)") (class "Default")
      (node (ref "R_OUT") (pin "P$2_SWITCH") (pinfunction "SWITCH_P$2_SWITCH") (pintype "passive"))
    )
  )
)
